# multi-pcb-cruisecontrol.net
KiCad netlist of a schematic drawn in EAGLE
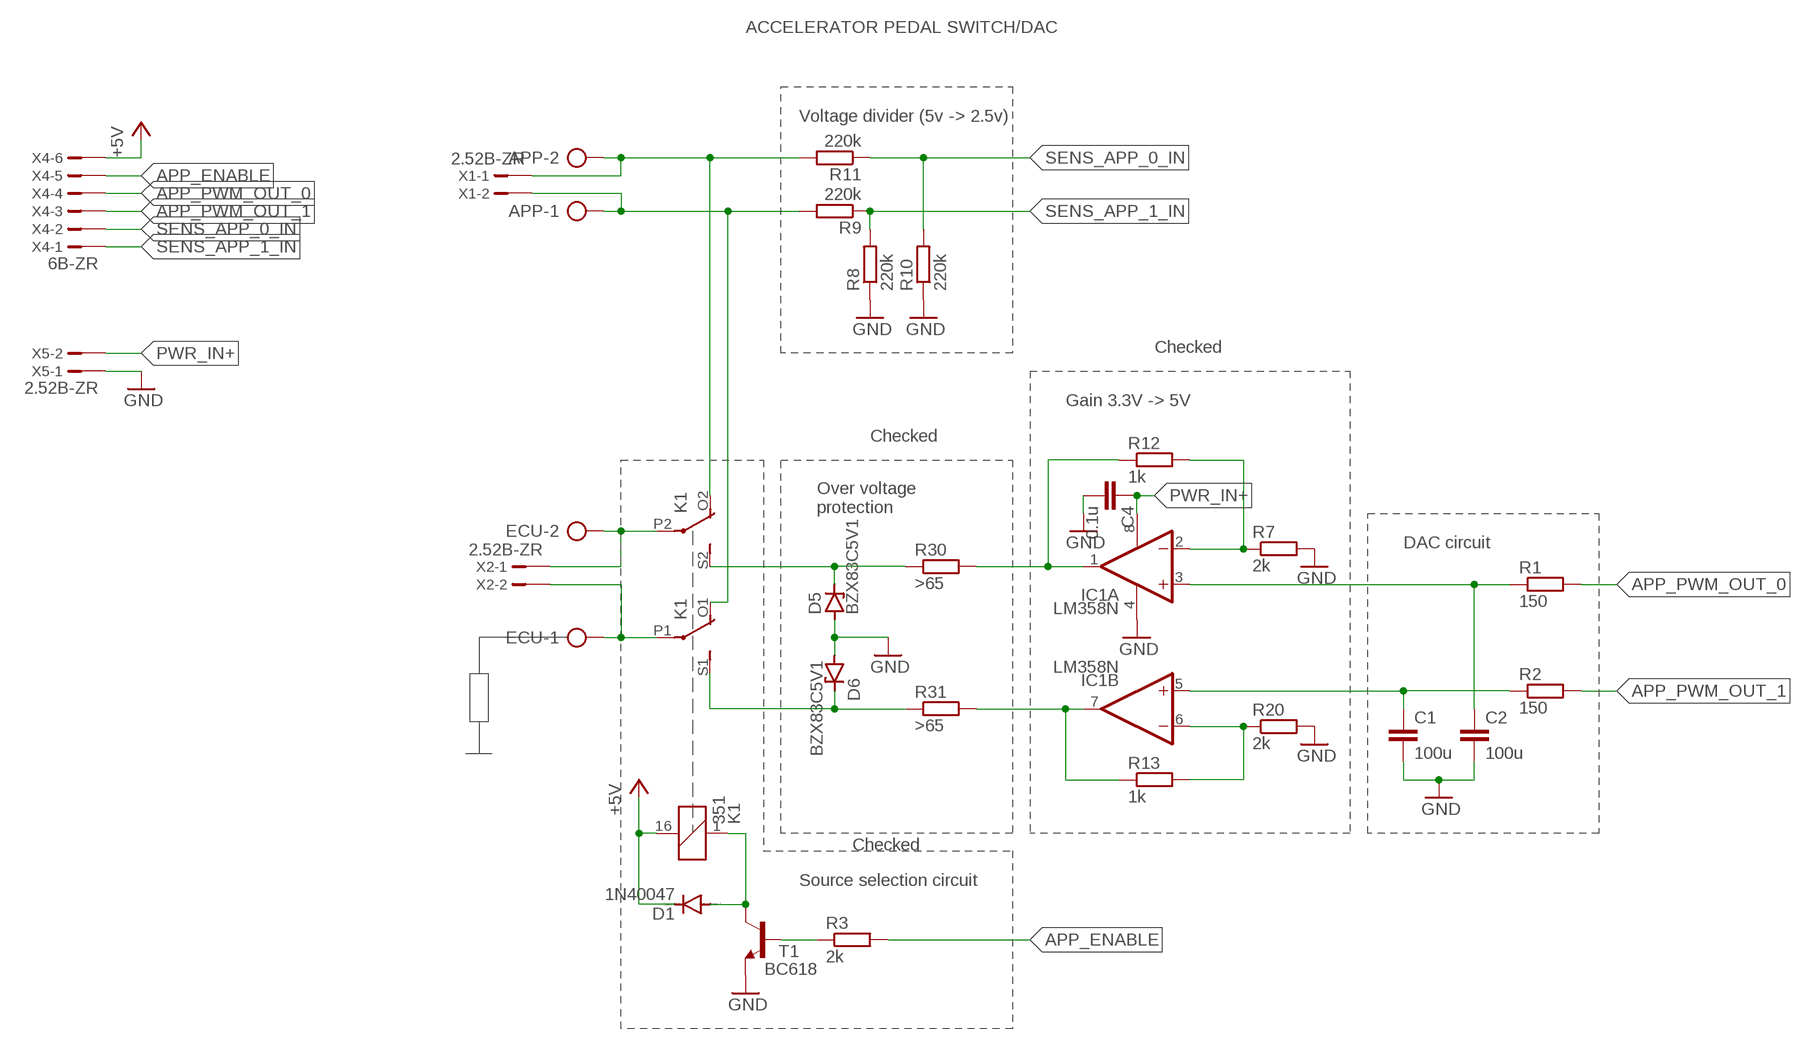
[diagram p0: schematic, sheet 1]

(export (version "E")
  (design (tool "Eeschema 10.0.6"))
  (components
    (comp (ref "APP")
      (value "AK300/2")
      (footprint "eagle-import:AK300_2")
      (libsource (lib "eagle-import") (part "AK300/2"))
    )
    (comp (ref "C1")
      (value "100u")
      (footprint "eagle-import:C025-050X050")
      (libsource (lib "eagle-import") (part "C-EU025-050X050"))
    )
    (comp (ref "C2")
      (value "100u")
      (footprint "eagle-import:C025-050X050")
      (libsource (lib "eagle-import") (part "C-EU025-050X050"))
    )
    (comp (ref "C4")
      (value "0.1u")
      (footprint "eagle-import:C025-050X050")
      (libsource (lib "eagle-import") (part "C-EU025-050X050"))
    )
    (comp (ref "D1")
      (value "1N40047")
      (footprint "eagle-import:DO41-7.6")
      (libsource (lib "eagle-import") (part "1N40047"))
    )
    (comp (ref "D5")
      (value "BZX83C5V1")
      (footprint "eagle-import:DO41Z7.6")
      (libsource (lib "eagle-import") (part "BZX857"))
    )
    (comp (ref "D6")
      (value "BZX83C5V1")
      (footprint "eagle-import:DO41Z7.6")
      (libsource (lib "eagle-import") (part "BZX857"))
    )
    (comp (ref "ECU")
      (value "AK300/2")
      (footprint "eagle-import:AK300_2")
      (libsource (lib "eagle-import") (part "AK300/2"))
    )
    (comp (ref "IC1")
      (value "LM358N")
      (footprint "eagle-import:DIL08")
      (libsource (lib "eagle-import") (part "LM358N"))
    )
    (comp (ref "K1")
      (value "351")
      (footprint "eagle-import:351")
      (libsource (lib "eagle-import") (part "351"))
    )
    (comp (ref "R1")
      (value "150")
      (footprint "eagle-import:0207_7")
      (libsource (lib "eagle-import") (part "R-EU_0207/7"))
    )
    (comp (ref "R2")
      (value "150")
      (footprint "eagle-import:0207_7")
      (libsource (lib "eagle-import") (part "R-EU_0207/7"))
    )
    (comp (ref "R3")
      (value "2k")
      (footprint "eagle-import:0207_7")
      (libsource (lib "eagle-import") (part "R-EU_0207/7"))
    )
    (comp (ref "R7")
      (value "2k")
      (footprint "eagle-import:0207_7")
      (libsource (lib "eagle-import") (part "R-EU_0207/7"))
    )
    (comp (ref "R8")
      (value "220k")
      (footprint "eagle-import:0207_7")
      (libsource (lib "eagle-import") (part "R-EU_0207/7"))
    )
    (comp (ref "R9")
      (value "220k")
      (footprint "eagle-import:0207_7")
      (libsource (lib "eagle-import") (part "R-EU_0207/7"))
    )
    (comp (ref "R10")
      (value "220k")
      (footprint "eagle-import:0207_7")
      (libsource (lib "eagle-import") (part "R-EU_0207/7"))
    )
    (comp (ref "R11")
      (value "220k")
      (footprint "eagle-import:0207_7")
      (libsource (lib "eagle-import") (part "R-EU_0207/7"))
    )
    (comp (ref "R12")
      (value "1k")
      (footprint "eagle-import:0207_7")
      (libsource (lib "eagle-import") (part "R-EU_0207/7"))
    )
    (comp (ref "R13")
      (value "1k")
      (footprint "eagle-import:0207_7")
      (libsource (lib "eagle-import") (part "R-EU_0207/7"))
    )
    (comp (ref "R20")
      (value "2k")
      (footprint "eagle-import:0207_7")
      (libsource (lib "eagle-import") (part "R-EU_0207/7"))
    )
    (comp (ref "R30")
      (value ">65")
      (footprint "eagle-import:0207_7")
      (libsource (lib "eagle-import") (part "R-EU_0207/7"))
    )
    (comp (ref "R31")
      (value ">65")
      (footprint "eagle-import:0207_7")
      (libsource (lib "eagle-import") (part "R-EU_0207/7"))
    )
    (comp (ref "T1")
      (value "BC618")
      (footprint "eagle-import:TO92-EBC")
      (libsource (lib "eagle-import") (part "BC618"))
    )
    (comp (ref "X1")
      (value "2.52B-ZR")
      (footprint "eagle-import:B2B-ZR2.5")
      (libsource (lib "eagle-import") (part "?2B-ZR2.5"))
    )
    (comp (ref "X2")
      (value "2.52B-ZR")
      (footprint "eagle-import:B2B-ZR2.5")
      (libsource (lib "eagle-import") (part "?2B-ZR2.5"))
    )
    (comp (ref "X4")
      (value "6B-ZR")
      (footprint "eagle-import:B6B-ZR2.5")
      (libsource (lib "eagle-import") (part "?6B-ZR"))
    )
    (comp (ref "X5")
      (value "2.52B-ZR")
      (footprint "eagle-import:B2B-ZR2.5")
      (libsource (lib "eagle-import") (part "?2B-ZR2.5"))
    )
  )
  (nets
    (net (code "1") (name "+5V") (class "Default")
      (node (ref "D1") (pin "C") (pinfunction "C_C") (pintype "passive"))
      (node (ref "K1") (pin "16") (pinfunction "2_16") (pintype "passive"))
      (node (ref "X4") (pin "6") (pinfunction "1_6") (pintype "passive"))
    )
    (net (code "2") (name "APP_ENABLE") (class "Default")
      (node (ref "R3") (pin "2") (pinfunction "2_2") (pintype "passive"))
      (node (ref "X4") (pin "5") (pinfunction "1_5") (pintype "passive"))
    )
    (net (code "3") (name "APP_PWM_OUT_0") (class "Default")
      (node (ref "R1") (pin "2") (pinfunction "2_2") (pintype "passive"))
      (node (ref "X4") (pin "4") (pinfunction "1_4") (pintype "passive"))
    )
    (net (code "4") (name "APP_PWM_OUT_1") (class "Default")
      (node (ref "R2") (pin "2") (pinfunction "2_2") (pintype "passive"))
      (node (ref "X4") (pin "3") (pinfunction "1_3") (pintype "passive"))
    )
    (net (code "5") (name "GND") (class "Default")
      (node (ref "C1") (pin "2") (pinfunction "2_2") (pintype "passive"))
      (node (ref "C2") (pin "2") (pinfunction "2_2") (pintype "passive"))
      (node (ref "C4") (pin "2") (pinfunction "2_2") (pintype "passive"))
      (node (ref "D5") (pin "A") (pinfunction "A_A") (pintype "passive"))
      (node (ref "D6") (pin "A") (pinfunction "A_A") (pintype "passive"))
      (node (ref "IC1") (pin "4") (pinfunction "V-_4") (pintype "power_in"))
      (node (ref "R10") (pin "1") (pinfunction "1_1") (pintype "passive"))
      (node (ref "R20") (pin "2") (pinfunction "2_2") (pintype "passive"))
      (node (ref "R7") (pin "2") (pinfunction "2_2") (pintype "passive"))
      (node (ref "R8") (pin "1") (pinfunction "1_1") (pintype "passive"))
      (node (ref "T1") (pin "E") (pinfunction "E_E") (pintype "passive"))
      (node (ref "X5") (pin "1") (pinfunction "1_1") (pintype "passive"))
    )
    (net (code "6") (name "Net-(APPA-KL)") (class "Default")
      (node (ref "APP") (pin "1") (pinfunction "KL_1") (pintype "passive"))
      (node (ref "K1") (pin "O1") (pinfunction "O_O1") (pintype "passive"))
      (node (ref "R9") (pin "2") (pinfunction "2_2") (pintype "passive"))
      (node (ref "X1") (pin "2") (pinfunction "1_2") (pintype "passive"))
    )
    (net (code "7") (name "Net-(APPB-KL)") (class "Default")
      (node (ref "APP") (pin "2") (pinfunction "KL_2") (pintype "passive"))
      (node (ref "K1") (pin "O2") (pinfunction "O_O2") (pintype "passive"))
      (node (ref "R11") (pin "2") (pinfunction "2_2") (pintype "passive"))
      (node (ref "X1") (pin "1") (pinfunction "1_1") (pintype "passive"))
    )
    (net (code "8") (name "Net-(D1-PadA)") (class "Default")
      (node (ref "D1") (pin "A") (pinfunction "A_A") (pintype "passive"))
      (node (ref "K1") (pin "1") (pinfunction "1_1") (pintype "passive"))
      (node (ref "T1") (pin "C") (pinfunction "C_C") (pintype "passive"))
    )
    (net (code "9") (name "Net-(ECUA-KL)") (class "Default")
      (node (ref "ECU") (pin "1") (pinfunction "KL_1") (pintype "passive"))
      (node (ref "K1") (pin "P1") (pinfunction "P_P1") (pintype "passive"))
      (node (ref "X2") (pin "2") (pinfunction "1_2") (pintype "passive"))
    )
    (net (code "10") (name "Net-(ECUB-KL)") (class "Default")
      (node (ref "ECU") (pin "2") (pinfunction "KL_2") (pintype "passive"))
      (node (ref "K1") (pin "P2") (pinfunction "P_P2") (pintype "passive"))
      (node (ref "X2") (pin "1") (pinfunction "1_1") (pintype "passive"))
    )
    (net (code "11") (name "Net-(IC1A-+IN)") (class "Default")
      (node (ref "C2") (pin "1") (pinfunction "1_1") (pintype "passive"))
      (node (ref "IC1") (pin "3") (pinfunction "+IN_3") (pintype "input"))
      (node (ref "R1") (pin "1") (pinfunction "1_1") (pintype "passive"))
    )
    (net (code "12") (name "Net-(IC1A--IN)") (class "Default")
      (node (ref "IC1") (pin "2") (pinfunction "-IN_2") (pintype "input"))
      (node (ref "R12") (pin "2") (pinfunction "2_2") (pintype "passive"))
      (node (ref "R7") (pin "1") (pinfunction "1_1") (pintype "passive"))
    )
    (net (code "13") (name "Net-(IC1A-OUT)") (class "Default")
      (node (ref "IC1") (pin "1") (pinfunction "OUT_1") (pintype "output"))
      (node (ref "R12") (pin "1") (pinfunction "1_1") (pintype "passive"))
      (node (ref "R30") (pin "2") (pinfunction "2_2") (pintype "passive"))
    )
    (net (code "14") (name "Net-(IC1B-+IN)") (class "Default")
      (node (ref "C1") (pin "1") (pinfunction "1_1") (pintype "passive"))
      (node (ref "IC1") (pin "5") (pinfunction "+IN_5") (pintype "input"))
      (node (ref "R2") (pin "1") (pinfunction "1_1") (pintype "passive"))
    )
    (net (code "15") (name "Net-(IC1B--IN)") (class "Default")
      (node (ref "IC1") (pin "6") (pinfunction "-IN_6") (pintype "input"))
      (node (ref "R13") (pin "2") (pinfunction "2_2") (pintype "passive"))
      (node (ref "R20") (pin "1") (pinfunction "1_1") (pintype "passive"))
    )
    (net (code "16") (name "Net-(IC1B-OUT)") (class "Default")
      (node (ref "IC1") (pin "7") (pinfunction "OUT_7") (pintype "output"))
      (node (ref "R13") (pin "1") (pinfunction "1_1") (pintype "passive"))
      (node (ref "R31") (pin "2") (pinfunction "2_2") (pintype "passive"))
    )
    (net (code "17") (name "Net-(K1B-S)") (class "Default")
      (node (ref "D6") (pin "C") (pinfunction "C_C") (pintype "passive"))
      (node (ref "K1") (pin "S1") (pinfunction "S_S1") (pintype "passive"))
      (node (ref "R31") (pin "1") (pinfunction "1_1") (pintype "passive"))
    )
    (net (code "18") (name "Net-(K1C-S)") (class "Default")
      (node (ref "D5") (pin "C") (pinfunction "C_C") (pintype "passive"))
      (node (ref "K1") (pin "S2") (pinfunction "S_S2") (pintype "passive"))
      (node (ref "R30") (pin "1") (pinfunction "1_1") (pintype "passive"))
    )
    (net (code "19") (name "Net-(R3-Pad1)") (class "Default")
      (node (ref "R3") (pin "1") (pinfunction "1_1") (pintype "passive"))
      (node (ref "T1") (pin "B") (pinfunction "B_B") (pintype "passive"))
    )
    (net (code "20") (name "PWR_IN+") (class "Default")
      (node (ref "C4") (pin "1") (pinfunction "1_1") (pintype "passive"))
      (node (ref "IC1") (pin "8") (pinfunction "V+_8") (pintype "power_in"))
      (node (ref "X5") (pin "2") (pinfunction "1_2") (pintype "passive"))
    )
    (net (code "21") (name "SENS_APP_0_IN") (class "Default")
      (node (ref "R10") (pin "2") (pinfunction "2_2") (pintype "passive"))
      (node (ref "R11") (pin "1") (pinfunction "1_1") (pintype "passive"))
      (node (ref "X4") (pin "2") (pinfunction "1_2") (pintype "passive"))
    )
    (net (code "22") (name "SENS_APP_1_IN") (class "Default")
      (node (ref "R8") (pin "2") (pinfunction "2_2") (pintype "passive"))
      (node (ref "R9") (pin "1") (pinfunction "1_1") (pintype "passive"))
      (node (ref "X4") (pin "1") (pinfunction "1_1") (pintype "passive"))
    )
  )
)
